# DDS_controller.net
KiCad netlist of a schematic drawn in Altium Designer
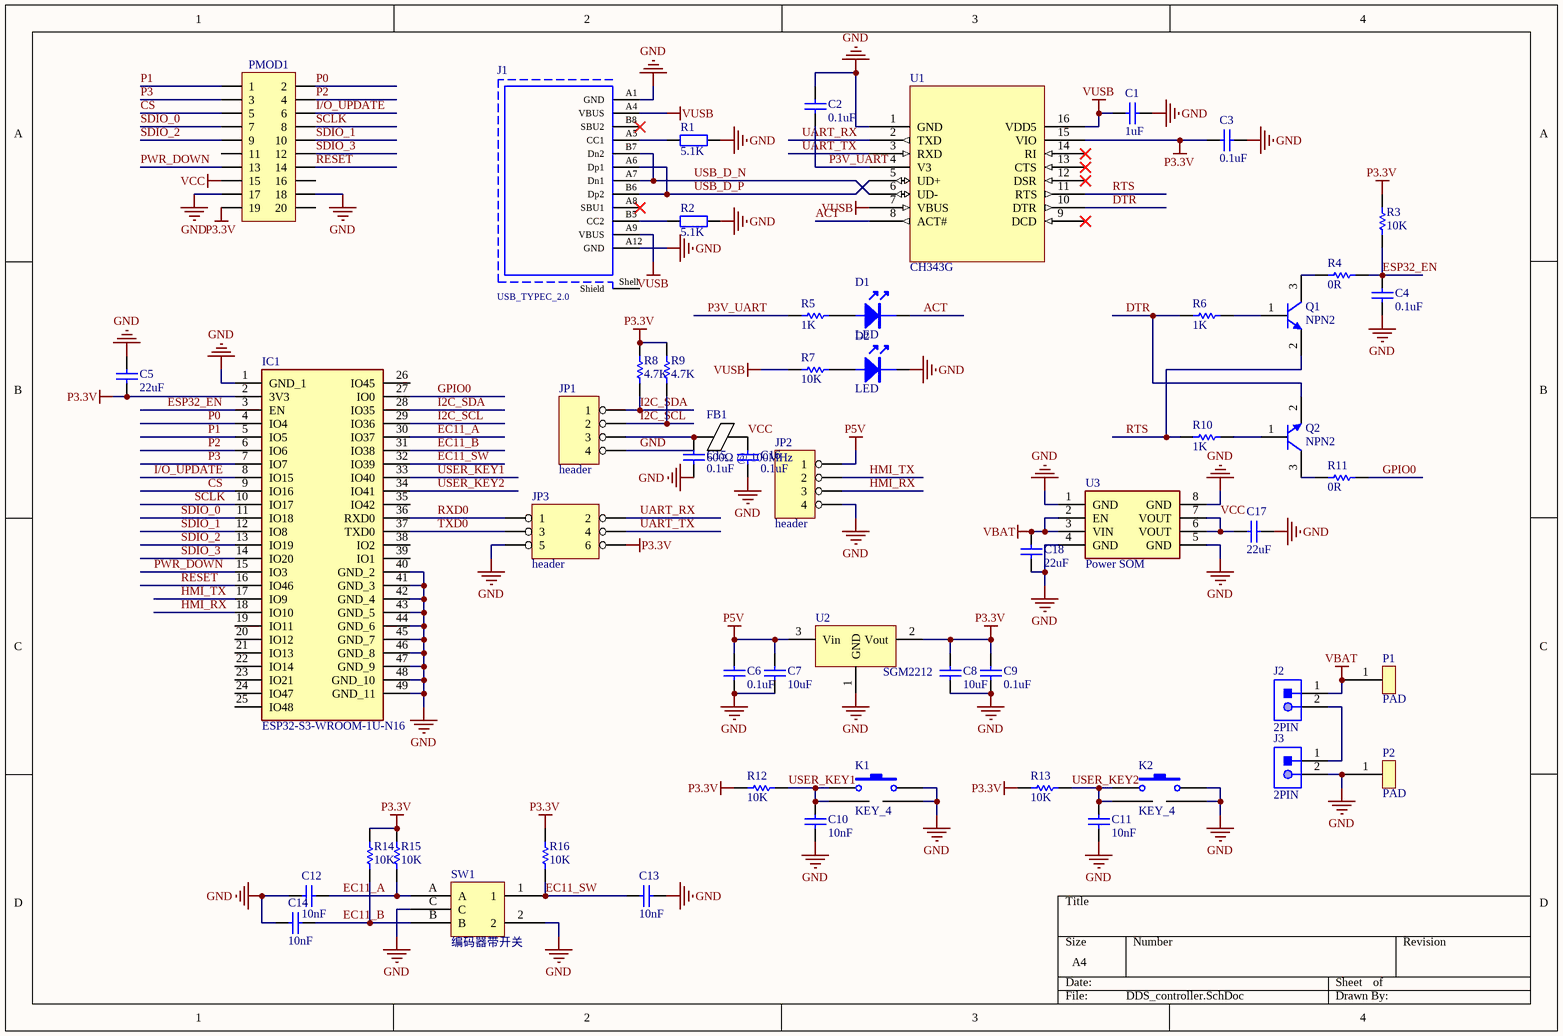
[diagram p0: DDS_controller.SchDoc]

(export (version "E")
  (design (tool "Eeschema 10.0.6"))
  (components
    (comp (ref "C1")
      (value "1uF")
      (footprint "0402L")
      (description "Capacitor")
      (fields (field (name "PUBLISHER") "Altium Limited"))
      (libsource (lib "My Footprint") (part "CAP"))
    )
    (comp (ref "C2")
      (value "0.1uF")
      (footprint "0402L")
      (description "Capacitor")
      (fields (field (name "PUBLISHER") "Altium Limited"))
      (libsource (lib "My Footprint") (part "CAP"))
    )
    (comp (ref "C3")
      (value "0.1uF")
      (footprint "0402L")
      (description "Capacitor")
      (fields (field (name "PUBLISHER") "Altium Limited"))
      (libsource (lib "My Footprint") (part "CAP"))
    )
    (comp (ref "C4")
      (value "0.1uF")
      (footprint "0402L")
      (description "Capacitor")
      (fields (field (name "PUBLISHER") "Altium Limited"))
      (libsource (lib "My Footprint") (part "CAP"))
    )
    (comp (ref "C5")
      (value "22uF")
      (footprint "0805")
      (description "Capacitor")
      (fields (field (name "PUBLISHER") "Altium Limited"))
      (libsource (lib "My Footprint") (part "CAP"))
    )
    (comp (ref "C6")
      (value "0.1uF")
      (footprint "0402L")
      (description "Capacitor")
      (fields (field (name "PUBLISHER") "Altium Limited"))
      (libsource (lib "My Footprint") (part "CAP"))
    )
    (comp (ref "C7")
      (value "10uF")
      (footprint "0805")
      (description "Capacitor")
      (fields (field (name "PUBLISHER") "Altium Limited"))
      (libsource (lib "My Footprint") (part "CAP"))
    )
    (comp (ref "C8")
      (value "10uF")
      (footprint "0805")
      (description "Capacitor")
      (fields (field (name "PUBLISHER") "Altium Limited"))
      (libsource (lib "My Footprint") (part "CAP"))
    )
    (comp (ref "C9")
      (value "0.1uF")
      (footprint "0402L")
      (description "Capacitor")
      (fields (field (name "PUBLISHER") "Altium Limited"))
      (libsource (lib "My Footprint") (part "CAP"))
    )
    (comp (ref "C10")
      (value "10nF")
      (footprint "0402L")
      (description "Capacitor")
      (fields (field (name "PUBLISHER") "Altium Limited"))
      (libsource (lib "My Footprint") (part "CAP"))
    )
    (comp (ref "C11")
      (value "10nF")
      (footprint "0402L")
      (description "Capacitor")
      (fields (field (name "PUBLISHER") "Altium Limited"))
      (libsource (lib "My Footprint") (part "CAP"))
    )
    (comp (ref "C12")
      (value "10nF")
      (footprint "0402L")
      (description "Capacitor")
      (fields (field (name "PUBLISHER") "Altium Limited"))
      (libsource (lib "My Footprint") (part "CAP"))
    )
    (comp (ref "C13")
      (value "10nF")
      (footprint "0402L")
      (description "Capacitor")
      (fields (field (name "PUBLISHER") "Altium Limited"))
      (libsource (lib "My Footprint") (part "CAP"))
    )
    (comp (ref "C14")
      (value "10nF")
      (footprint "0402L")
      (description "Capacitor")
      (fields (field (name "PUBLISHER") "Altium Limited"))
      (libsource (lib "My Footprint") (part "CAP"))
    )
    (comp (ref "C15")
      (value "0.1uF")
      (footprint "0603_C")
      (description "Capacitor")
      (fields (field (name "PUBLISHER") "Altium Limited"))
      (libsource (lib "My Footprint") (part "CAP"))
    )
    (comp (ref "C16")
      (value "0.1uF")
      (footprint "0603_C")
      (description "Capacitor")
      (fields (field (name "PUBLISHER") "Altium Limited"))
      (libsource (lib "My Footprint") (part "CAP"))
    )
    (comp (ref "C17")
      (value "22uF")
      (footprint "0805")
      (description "Capacitor")
      (fields (field (name "PUBLISHER") "Altium Limited"))
      (libsource (lib "My Footprint") (part "CAP"))
    )
    (comp (ref "C18")
      (value "22uF")
      (footprint "0805")
      (description "Capacitor")
      (fields (field (name "PUBLISHER") "Altium Limited"))
      (libsource (lib "My Footprint") (part "CAP"))
    )
    (comp (ref "D1")
      (value "LED")
      (footprint "0603_LED")
      (description "LED 发光二极管")
      (libsource (lib "My Footprint") (part "LED"))
    )
    (comp (ref "D2")
      (value "LED")
      (footprint "0603_LED")
      (description "LED 发光二极管")
      (libsource (lib "My Footprint") (part "LED"))
    )
    (comp (ref "FB1")
      (value "600Ω @ 100MHz")
      (footprint "0805")
      (description "磁珠 600Ω @ 100MHz")
      (libsource (lib "My Footprint") (part "FB"))
    )
    (comp (ref "IC1")
      (value "ESP32-S3-WROOM-1U-N16")
      (footprint "SamacSys:ESP32S3WROOM1UN16")
      (description "Integrated Circuit")
      (fields (field (name "MOUSER PART NUMBER") "356-ESP32S3WROM1UN16"))
      (libsource (lib "SamacSys") (part "ESP32-S3-WROOM-1U-N16"))
    )
    (comp (ref "J1")
      (value "USB_TYPEC_2.0")
      (footprint "USB_TYPEC_2.0_Horizontal_SMT")
      (description "USB 3.1 Type C Receptacle WR-COM, Horizontal, SMT / THT")
      (fields (field (name "PART NUMBER") "632723300011") (field (name "PUBLISHER") "Wurth Elektronik"))
      (libsource (lib "RegenovoPcbLib") (part "USB_TYPEC_2.0"))
    )
    (comp (ref "J2")
      (value "2PIN")
      (footprint "XH2.54-LI-2P")
      (libsource (lib "My Footprint") (part "HEADER 2PIN"))
    )
    (comp (ref "J3")
      (value "2PIN")
      (footprint "XH2.54-LI-2P")
      (libsource (lib "My Footprint") (part "HEADER 2PIN"))
    )
    (comp (ref "JP1")
      (value "header")
      (footprint "header4")
      (libsource (lib "My Footprint") (part "HEADER 4"))
    )
    (comp (ref "JP2")
      (value "header")
      (footprint "header4")
      (libsource (lib "My Footprint") (part "HEADER 4"))
    )
    (comp (ref "JP3")
      (value "header")
      (footprint "header2X3")
      (libsource (lib "My Footprint") (part "HEADER 3X2"))
    )
    (comp (ref "K1")
      (value "KEY_4")
      (footprint "KEY5*5")
      (description "Switch")
      (fields (field (name "PUBLISHER") "Altium Limited"))
      (libsource (lib "My Footprint") (part "KEY_4"))
    )
    (comp (ref "K2")
      (value "KEY_4")
      (footprint "KEY5*5")
      (description "Switch")
      (fields (field (name "PUBLISHER") "Altium Limited"))
      (libsource (lib "My Footprint") (part "KEY_4"))
    )
    (comp (ref "P1") (value "PAD") (footprint "PAD") (libsource (lib "My Footprint") (part "PAD")))
    (comp (ref "P2") (value "PAD") (footprint "PAD") (libsource (lib "My Footprint") (part "PAD")))
    (comp (ref "PMOD1")
      (value "Header 2X10")
      (footprint "header2X10")
      (description "10*2P接插件")
      (libsource (lib "2x10_PMOD") (part "Header 10X2"))
    )
    (comp (ref "Q1")
      (value "NPN2")
      (footprint "SOT-23-3")
      (description "贴片")
      (libsource (lib "My Footprint") (part "NPN2"))
    )
    (comp (ref "Q2")
      (value "NPN2")
      (footprint "SOT-23-3")
      (description "贴片")
      (libsource (lib "My Footprint") (part "NPN2"))
    )
    (comp (ref "R1")
      (value "5.1K")
      (footprint "R0402")
      (description "Resistor")
      (fields (field (name "Comment") "Res") (field (name "PUBLISHER") "Altium Limited"))
      (libsource (lib "RegenovoPcbLib") (part "Res"))
    )
    (comp (ref "R2")
      (value "5.1K")
      (footprint "R0402")
      (description "Resistor")
      (fields (field (name "Comment") "Res") (field (name "PUBLISHER") "Altium Limited"))
      (libsource (lib "RegenovoPcbLib") (part "Res"))
    )
    (comp (ref "R3")
      (value "10K")
      (footprint "0402L")
      (description "Resistor")
      (fields (field (name "PUBLISHER") "Altium Limited"))
      (libsource (lib "My Footprint") (part "RES"))
    )
    (comp (ref "R4")
      (value "0R")
      (footprint "0402L")
      (description "Resistor")
      (fields (field (name "PUBLISHER") "Altium Limited"))
      (libsource (lib "My Footprint") (part "RES"))
    )
    (comp (ref "R5")
      (value "1K")
      (footprint "0402L")
      (description "Resistor")
      (fields (field (name "PUBLISHER") "Altium Limited"))
      (libsource (lib "My Footprint") (part "RES"))
    )
    (comp (ref "R6")
      (value "1K")
      (footprint "0402L")
      (description "Resistor")
      (fields (field (name "PUBLISHER") "Altium Limited"))
      (libsource (lib "My Footprint") (part "RES"))
    )
    (comp (ref "R7")
      (value "10K")
      (footprint "0402L")
      (description "Resistor")
      (fields (field (name "PUBLISHER") "Altium Limited"))
      (libsource (lib "My Footprint") (part "RES"))
    )
    (comp (ref "R8")
      (value "4.7K")
      (footprint "0402L")
      (description "Resistor")
      (fields (field (name "PUBLISHER") "Altium Limited"))
      (libsource (lib "My Footprint") (part "RES"))
    )
    (comp (ref "R9")
      (value "4.7K")
      (footprint "0402L")
      (description "Resistor")
      (fields (field (name "PUBLISHER") "Altium Limited"))
      (libsource (lib "My Footprint") (part "RES"))
    )
    (comp (ref "R10")
      (value "1K")
      (footprint "0402L")
      (description "Resistor")
      (fields (field (name "PUBLISHER") "Altium Limited"))
      (libsource (lib "My Footprint") (part "RES"))
    )
    (comp (ref "R11")
      (value "0R")
      (footprint "0402L")
      (description "Resistor")
      (fields (field (name "PUBLISHER") "Altium Limited"))
      (libsource (lib "My Footprint") (part "RES"))
    )
    (comp (ref "R12")
      (value "10K")
      (footprint "0402L")
      (description "Resistor")
      (fields (field (name "PUBLISHER") "Altium Limited"))
      (libsource (lib "My Footprint") (part "RES"))
    )
    (comp (ref "R13")
      (value "10K")
      (footprint "0402L")
      (description "Resistor")
      (fields (field (name "PUBLISHER") "Altium Limited"))
      (libsource (lib "My Footprint") (part "RES"))
    )
    (comp (ref "R14")
      (value "10K")
      (footprint "0402L")
      (description "Resistor")
      (fields (field (name "PUBLISHER") "Altium Limited"))
      (libsource (lib "My Footprint") (part "RES"))
    )
    (comp (ref "R15")
      (value "10K")
      (footprint "0402L")
      (description "Resistor")
      (fields (field (name "PUBLISHER") "Altium Limited"))
      (libsource (lib "My Footprint") (part "RES"))
    )
    (comp (ref "R16")
      (value "10K")
      (footprint "0402L")
      (description "Resistor")
      (fields (field (name "PUBLISHER") "Altium Limited"))
      (libsource (lib "My Footprint") (part "RES"))
    )
    (comp (ref "SW1") (value "编码器带开关") (footprint "EC11") (libsource (lib "My Footprint") (part "EC11")))
    (comp (ref "U1")
      (value "CH343G")
      (footprint "SOP16")
      (description "USB to high speed enhanced TTL Serial / UART")
      (libsource (lib "SamacSys") (part "CH343G"))
    )
    (comp (ref "U2")
      (value "SGM2212")
      (footprint "SOT-223")
      (description "3.3V电压转换器AMS1117")
      (libsource (lib "My Footprint") (part "AMS1117"))
    )
    (comp (ref "U3")
      (value "Power SOM")
      (footprint "7A8300")
      (libsource (lib "power_module") (part "TPS7A8300"))
    )
  )
  (nets
    (net (code "1") (name "/ACT") (class "Default")
      (node (ref "D1") (pin "1") (pinfunction "K_1") (pintype "passive"))
      (node (ref "U1") (pin "8") (pinfunction "ACT#_8") (pintype "output"))
    )
    (net (code "2") (name "/CS") (class "Default")
      (node (ref "IC1") (pin "9") (pinfunction "IO16_9") (pintype "passive"))
      (node (ref "PMOD1") (pin "5") (pinfunction "5_5") (pintype "passive"))
    )
    (net (code "3") (name "/DTR") (class "Default")
      (node (ref "Q2") (pin "2") (pinfunction "E_2") (pintype "passive"))
      (node (ref "R6") (pin "1") (pinfunction "1_1") (pintype "passive"))
      (node (ref "U1") (pin "10") (pinfunction "DTR_10") (pintype "output"))
    )
    (net (code "4") (name "/EC11_A") (class "Default")
      (node (ref "C12") (pin "2") (pinfunction "2_2") (pintype "passive"))
      (node (ref "IC1") (pin "30") (pinfunction "IO37_30") (pintype "passive"))
      (node (ref "R15") (pin "1") (pinfunction "1_1") (pintype "passive"))
      (node (ref "SW1") (pin "A") (pinfunction "A_A") (pintype "passive"))
    )
    (net (code "5") (name "/EC11_B") (class "Default")
      (node (ref "C14") (pin "2") (pinfunction "2_2") (pintype "passive"))
      (node (ref "IC1") (pin "31") (pinfunction "IO38_31") (pintype "passive"))
      (node (ref "R14") (pin "1") (pinfunction "1_1") (pintype "passive"))
      (node (ref "SW1") (pin "B") (pinfunction "B_B") (pintype "passive"))
    )
    (net (code "6") (name "/EC11_SW") (class "Default")
      (node (ref "C13") (pin "2") (pinfunction "2_2") (pintype "passive"))
      (node (ref "IC1") (pin "32") (pinfunction "IO39_32") (pintype "passive"))
      (node (ref "R16") (pin "1") (pinfunction "1_1") (pintype "passive"))
      (node (ref "SW1") (pin "1") (pinfunction "1_1") (pintype "passive"))
    )
    (net (code "7") (name "/ESP32_EN") (class "Default")
      (node (ref "C4") (pin "2") (pinfunction "2_2") (pintype "passive"))
      (node (ref "IC1") (pin "3") (pinfunction "EN_3") (pintype "passive"))
      (node (ref "R3") (pin "1") (pinfunction "1_1") (pintype "passive"))
      (node (ref "R4") (pin "2") (pinfunction "2_2") (pintype "passive"))
    )
    (net (code "8") (name "/GPIO0") (class "Default")
      (node (ref "IC1") (pin "27") (pinfunction "IO0_27") (pintype "passive"))
      (node (ref "R11") (pin "2") (pinfunction "2_2") (pintype "passive"))
    )
    (net (code "9") (name "/HMI_RX") (class "Default")
      (node (ref "IC1") (pin "18") (pinfunction "IO10_18") (pintype "passive"))
      (node (ref "JP2") (pin "3") (pinfunction "3_3") (pintype "passive"))
    )
    (net (code "10") (name "/HMI_TX") (class "Default")
      (node (ref "IC1") (pin "17") (pinfunction "IO9_17") (pintype "passive"))
      (node (ref "JP2") (pin "2") (pinfunction "2_2") (pintype "passive"))
    )
    (net (code "11") (name "/I2C_SCL") (class "Default")
      (node (ref "IC1") (pin "29") (pinfunction "IO36_29") (pintype "passive"))
      (node (ref "JP1") (pin "2") (pinfunction "2_2") (pintype "passive"))
      (node (ref "R9") (pin "1") (pinfunction "1_1") (pintype "passive"))
    )
    (net (code "12") (name "/I2C_SDA") (class "Default")
      (node (ref "IC1") (pin "28") (pinfunction "IO35_28") (pintype "passive"))
      (node (ref "JP1") (pin "1") (pinfunction "1_1") (pintype "passive"))
      (node (ref "R8") (pin "1") (pinfunction "1_1") (pintype "passive"))
    )
    (net (code "13") (name "/I{slash}O_UPDATE") (class "Default")
      (node (ref "IC1") (pin "8") (pinfunction "IO15_8") (pintype "passive"))
      (node (ref "PMOD1") (pin "6") (pinfunction "6_6") (pintype "passive"))
    )
    (net (code "14") (name "/P0") (class "Default")
      (node (ref "IC1") (pin "4") (pinfunction "IO4_4") (pintype "passive"))
      (node (ref "PMOD1") (pin "2") (pinfunction "2_2") (pintype "passive"))
    )
    (net (code "15") (name "/P1") (class "Default")
      (node (ref "IC1") (pin "5") (pinfunction "IO5_5") (pintype "passive"))
      (node (ref "PMOD1") (pin "1") (pinfunction "1_1") (pintype "passive"))
    )
    (net (code "16") (name "/P2") (class "Default")
      (node (ref "IC1") (pin "6") (pinfunction "IO6_6") (pintype "passive"))
      (node (ref "PMOD1") (pin "4") (pinfunction "4_4") (pintype "passive"))
    )
    (net (code "17") (name "/P3") (class "Default")
      (node (ref "IC1") (pin "7") (pinfunction "IO7_7") (pintype "passive"))
      (node (ref "PMOD1") (pin "3") (pinfunction "3_3") (pintype "passive"))
    )
    (net (code "18") (name "/P3V_UART") (class "Default")
      (node (ref "C2") (pin "1") (pinfunction "1_1") (pintype "passive"))
      (node (ref "R5") (pin "1") (pinfunction "1_1") (pintype "passive"))
      (node (ref "U1") (pin "4") (pinfunction "V3_4") (pintype "power_in"))
    )
    (net (code "19") (name "/PWR_DOWN") (class "Default")
      (node (ref "IC1") (pin "15") (pinfunction "IO3_15") (pintype "passive"))
      (node (ref "PMOD1") (pin "13") (pinfunction "13_13") (pintype "passive"))
    )
    (net (code "20") (name "/RESET") (class "Default")
      (node (ref "IC1") (pin "16") (pinfunction "IO46_16") (pintype "passive"))
      (node (ref "PMOD1") (pin "14") (pinfunction "14_14") (pintype "passive"))
    )
    (net (code "21") (name "/RTS") (class "Default")
      (node (ref "Q1") (pin "2") (pinfunction "E_2") (pintype "passive"))
      (node (ref "R10") (pin "1") (pinfunction "1_1") (pintype "passive"))
      (node (ref "U1") (pin "11") (pinfunction "RTS_11") (pintype "output"))
    )
    (net (code "22") (name "/RXD0") (class "Default")
      (node (ref "IC1") (pin "36") (pinfunction "RXD0_36") (pintype "passive"))
      (node (ref "JP3") (pin "1") (pinfunction "1_1") (pintype "passive"))
    )
    (net (code "23") (name "/SCLK") (class "Default")
      (node (ref "IC1") (pin "10") (pinfunction "IO17_10") (pintype "passive"))
      (node (ref "PMOD1") (pin "8") (pinfunction "8_8") (pintype "passive"))
    )
    (net (code "24") (name "/SDIO_0") (class "Default")
      (node (ref "IC1") (pin "11") (pinfunction "IO18_11") (pintype "passive"))
      (node (ref "PMOD1") (pin "7") (pinfunction "7_7") (pintype "passive"))
    )
    (net (code "25") (name "/SDIO_1") (class "Default")
      (node (ref "IC1") (pin "12") (pinfunction "IO8_12") (pintype "passive"))
      (node (ref "PMOD1") (pin "10") (pinfunction "10_10") (pintype "passive"))
    )
    (net (code "26") (name "/SDIO_2") (class "Default")
      (node (ref "IC1") (pin "13") (pinfunction "IO19_13") (pintype "passive"))
      (node (ref "PMOD1") (pin "9") (pinfunction "9_9") (pintype "passive"))
    )
    (net (code "27") (name "/SDIO_3") (class "Default")
      (node (ref "IC1") (pin "14") (pinfunction "IO20_14") (pintype "passive"))
      (node (ref "PMOD1") (pin "12") (pinfunction "12_12") (pintype "passive"))
    )
    (net (code "28") (name "/TXD0") (class "Default")
      (node (ref "IC1") (pin "37") (pinfunction "TXD0_37") (pintype "passive"))
      (node (ref "JP3") (pin "3") (pinfunction "3_3") (pintype "passive"))
    )
    (net (code "29") (name "/UART_RX") (class "Default")
      (node (ref "JP3") (pin "2") (pinfunction "2_2") (pintype "passive"))
      (node (ref "U1") (pin "2") (pinfunction "TXD_2") (pintype "output"))
    )
    (net (code "30") (name "/UART_TX") (class "Default")
      (node (ref "JP3") (pin "4") (pinfunction "4_4") (pintype "passive"))
      (node (ref "U1") (pin "3") (pinfunction "RXD_3") (pintype "input"))
    )
    (net (code "31") (name "/USB_D_N") (class "Default")
      (node (ref "J1") (pin "A7") (pinfunction "Dn1_A7") (pintype "passive"))
      (node (ref "J1") (pin "B7") (pinfunction "Dn2_B7") (pintype "passive"))
      (node (ref "U1") (pin "6") (pinfunction "UD-_6") (pintype "bidirectional"))
    )
    (net (code "32") (name "/USB_D_P") (class "Default")
      (node (ref "J1") (pin "A6") (pinfunction "Dp1_A6") (pintype "passive"))
      (node (ref "J1") (pin "B6") (pinfunction "Dp2_B6") (pintype "passive"))
      (node (ref "U1") (pin "5") (pinfunction "UD+_5") (pintype "bidirectional"))
    )
    (net (code "33") (name "/USER_KEY1") (class "Default")
      (node (ref "C10") (pin "2") (pinfunction "2_2") (pintype "passive"))
      (node (ref "IC1") (pin "33") (pinfunction "IO40_33") (pintype "passive"))
      (node (ref "K1") (pin "1") (pinfunction "1_1") (pintype "passive"))
      (node (ref "K1") (pin "4") (pinfunction "4_4") (pintype "passive"))
      (node (ref "R12") (pin "1") (pinfunction "1_1") (pintype "passive"))
    )
    (net (code "34") (name "/USER_KEY2") (class "Default")
      (node (ref "C11") (pin "2") (pinfunction "2_2") (pintype "passive"))
      (node (ref "IC1") (pin "34") (pinfunction "IO41_34") (pintype "passive"))
      (node (ref "K2") (pin "1") (pinfunction "1_1") (pintype "passive"))
      (node (ref "K2") (pin "4") (pinfunction "4_4") (pintype "passive"))
      (node (ref "R13") (pin "1") (pinfunction "1_1") (pintype "passive"))
    )
    (net (code "35") (name "GND") (class "Default")
      (node (ref "C1") (pin "1") (pinfunction "1_1") (pintype "passive"))
      (node (ref "C10") (pin "1") (pinfunction "1_1") (pintype "passive"))
      (node (ref "C11") (pin "1") (pinfunction "1_1") (pintype "passive"))
      (node (ref "C12") (pin "1") (pinfunction "1_1") (pintype "passive"))
      (node (ref "C13") (pin "1") (pinfunction "1_1") (pintype "passive"))
      (node (ref "C14") (pin "1") (pinfunction "1_1") (pintype "passive"))
      (node (ref "C15") (pin "1") (pinfunction "1_1") (pintype "passive"))
      (node (ref "C16") (pin "1") (pinfunction "1_1") (pintype "passive"))
      (node (ref "C17") (pin "1") (pinfunction "1_1") (pintype "passive"))
      (node (ref "C18") (pin "2") (pinfunction "2_2") (pintype "passive"))
      (node (ref "C2") (pin "2") (pinfunction "2_2") (pintype "passive"))
      (node (ref "C3") (pin "2") (pinfunction "2_2") (pintype "passive"))
      (node (ref "C4") (pin "1") (pinfunction "1_1") (pintype "passive"))
      (node (ref "C5") (pin "2") (pinfunction "2_2") (pintype "passive"))
      (node (ref "C6") (pin "1") (pinfunction "1_1") (pintype "passive"))
      (node (ref "C7") (pin "1") (pinfunction "1_1") (pintype "passive"))
      (node (ref "C8") (pin "1") (pinfunction "1_1") (pintype "passive"))
      (node (ref "C9") (pin "1") (pinfunction "1_1") (pintype "passive"))
      (node (ref "D2") (pin "1") (pinfunction "K_1") (pintype "passive"))
      (node (ref "IC1") (pin "1") (pinfunction "GND_1_1") (pintype "passive"))
      (node (ref "IC1") (pin "40") (pinfunction "GND_2_40") (pintype "passive"))
      (node (ref "IC1") (pin "41") (pinfunction "GND_3_41") (pintype "passive"))
      (node (ref "IC1") (pin "42") (pinfunction "GND_4_42") (pintype "passive"))
      (node (ref "IC1") (pin "43") (pinfunction "GND_5_43") (pintype "passive"))
      (node (ref "IC1") (pin "44") (pinfunction "GND_6_44") (pintype "passive"))
      (node (ref "IC1") (pin "45") (pinfunction "GND_7_45") (pintype "passive"))
      (node (ref "IC1") (pin "46") (pinfunction "GND_8_46") (pintype "passive"))
      (node (ref "IC1") (pin "47") (pinfunction "GND_9_47") (pintype "passive"))
      (node (ref "IC1") (pin "48") (pinfunction "GND_10_48") (pintype "passive"))
      (node (ref "IC1") (pin "49") (pinfunction "GND_11_49") (pintype "passive"))
      (node (ref "J1") (pin "A1") (pinfunction "GND_A1") (pintype "passive"))
      (node (ref "J1") (pin "A12") (pinfunction "GND_A12") (pintype "passive"))
      (node (ref "J3") (pin "2") (pinfunction "2_2") (pintype "passive"))
      (node (ref "JP1") (pin "4") (pinfunction "4_4") (pintype "passive"))
      (node (ref "JP2") (pin "4") (pinfunction "4_4") (pintype "passive"))
      (node (ref "JP3") (pin "5") (pinfunction "5_5") (pintype "passive"))
      (node (ref "K1") (pin "2") (pinfunction "2_2") (pintype "passive"))
      (node (ref "K1") (pin "3") (pinfunction "3_3") (pintype "passive"))
      (node (ref "K2") (pin "2") (pinfunction "2_2") (pintype "passive"))
      (node (ref "K2") (pin "3") (pinfunction "3_3") (pintype "passive"))
      (node (ref "P2") (pin "1") (pintype "passive"))
      (node (ref "PMOD1") (pin "17") (pinfunction "17_17") (pintype "passive"))
      (node (ref "PMOD1") (pin "18") (pinfunction "18_18") (pintype "passive"))
      (node (ref "R1") (pin "2") (pinfunction "2_2") (pintype "passive"))
      (node (ref "R2") (pin "2") (pinfunction "2_2") (pintype "passive"))
      (node (ref "SW1") (pin "2") (pinfunction "2_2") (pintype "passive"))
      (node (ref "SW1") (pin "C") (pinfunction "C_C") (pintype "passive"))
      (node (ref "U1") (pin "1") (pinfunction "GND_1") (pintype "power_in"))
      (node (ref "U2") (pin "1") (pinfunction "GND_1") (pintype "passive"))
      (node (ref "U3") (pin "1") (pinfunction "GND_1") (pintype "passive"))
      (node (ref "U3") (pin "4") (pinfunction "GND_4") (pintype "passive"))
      (node (ref "U3") (pin "5") (pinfunction "GND_5") (pintype "passive"))
      (node (ref "U3") (pin "8") (pinfunction "GND_8") (pintype "passive"))
    )
    (net (code "36") (name "Net-(C15-Pad2)") (class "Default")
      (node (ref "C15") (pin "2") (pinfunction "2_2") (pintype "passive"))
      (node (ref "FB1") (pin "1") (pinfunction "1_1") (pintype "passive"))
      (node (ref "JP1") (pin "3") (pinfunction "3_3") (pintype "passive"))
    )
    (net (code "37") (name "Net-(D1-A)") (class "Default")
      (node (ref "D1") (pin "2") (pinfunction "A_2") (pintype "passive"))
      (node (ref "R5") (pin "2") (pinfunction "2_2") (pintype "passive"))
    )
    (net (code "38") (name "Net-(D2-A)") (class "Default")
      (node (ref "D2") (pin "2") (pinfunction "A_2") (pintype "passive"))
      (node (ref "R7") (pin "2") (pinfunction "2_2") (pintype "passive"))
    )
    (net (code "39") (name "Net-(J1-CC1)") (class "Default")
      (node (ref "J1") (pin "A5") (pinfunction "CC1_A5") (pintype "passive"))
      (node (ref "R1") (pin "1") (pinfunction "1_1") (pintype "passive"))
    )
    (net (code "40") (name "Net-(J1-CC2)") (class "Default")
      (node (ref "J1") (pin "B5") (pinfunction "CC2_B5") (pintype "passive"))
      (node (ref "R2") (pin "1") (pinfunction "1_1") (pintype "passive"))
    )
    (net (code "41") (name "Net-(J2-Pad2)") (class "Default")
      (node (ref "J2") (pin "2") (pinfunction "2_2") (pintype "passive"))
      (node (ref "J3") (pin "1") (pinfunction "1_1") (pintype "passive"))
    )
    (net (code "42") (name "Net-(Q1-B)") (class "Default")
      (node (ref "Q1") (pin "1") (pinfunction "B_1") (pintype "passive"))
      (node (ref "R6") (pin "2") (pinfunction "2_2") (pintype "passive"))
    )
    (net (code "43") (name "Net-(Q1-C)") (class "Default")
      (node (ref "Q1") (pin "3") (pinfunction "C_3") (pintype "passive"))
      (node (ref "R4") (pin "1") (pinfunction "1_1") (pintype "passive"))
    )
    (net (code "44") (name "Net-(Q2-B)") (class "Default")
      (node (ref "Q2") (pin "1") (pinfunction "B_1") (pintype "passive"))
      (node (ref "R10") (pin "2") (pinfunction "2_2") (pintype "passive"))
    )
    (net (code "45") (name "Net-(Q2-C)") (class "Default")
      (node (ref "Q2") (pin "3") (pinfunction "C_3") (pintype "passive"))
      (node (ref "R11") (pin "1") (pinfunction "1_1") (pintype "passive"))
    )
    (net (code "46") (name "P3.3V") (class "Default")
      (node (ref "C3") (pin "1") (pinfunction "1_1") (pintype "passive"))
      (node (ref "C5") (pin "1") (pinfunction "1_1") (pintype "passive"))
      (node (ref "C8") (pin "2") (pinfunction "2_2") (pintype "passive"))
      (node (ref "C9") (pin "2") (pinfunction "2_2") (pintype "passive"))
      (node (ref "IC1") (pin "2") (pinfunction "3V3_2") (pintype "passive"))
      (node (ref "JP3") (pin "6") (pinfunction "6_6") (pintype "passive"))
      (node (ref "PMOD1") (pin "19") (pinfunction "19_19") (pintype "passive"))
      (node (ref "R12") (pin "2") (pinfunction "2_2") (pintype "passive"))
      (node (ref "R13") (pin "2") (pinfunction "2_2") (pintype "passive"))
      (node (ref "R14") (pin "2") (pinfunction "2_2") (pintype "passive"))
      (node (ref "R15") (pin "2") (pinfunction "2_2") (pintype "passive"))
      (node (ref "R16") (pin "2") (pinfunction "2_2") (pintype "passive"))
      (node (ref "R3") (pin "2") (pinfunction "2_2") (pintype "passive"))
      (node (ref "R8") (pin "2") (pinfunction "2_2") (pintype "passive"))
      (node (ref "R9") (pin "2") (pinfunction "2_2") (pintype "passive"))
      (node (ref "U1") (pin "15") (pinfunction "VIO_15") (pintype "power_in"))
      (node (ref "U2") (pin "2") (pinfunction "Vout_2") (pintype "passive"))
    )
    (net (code "47") (name "P5V") (class "Default")
      (node (ref "C6") (pin "2") (pinfunction "2_2") (pintype "passive"))
      (node (ref "C7") (pin "2") (pinfunction "2_2") (pintype "passive"))
      (node (ref "JP2") (pin "1") (pinfunction "1_1") (pintype "passive"))
      (node (ref "U2") (pin "3") (pinfunction "Vin_3") (pintype "passive"))
    )
    (net (code "48") (name "VBAT") (class "Default")
      (node (ref "C18") (pin "1") (pinfunction "1_1") (pintype "passive"))
      (node (ref "J2") (pin "1") (pinfunction "1_1") (pintype "passive"))
      (node (ref "P1") (pin "1") (pintype "passive"))
      (node (ref "U3") (pin "2") (pinfunction "EN_2") (pintype "passive"))
      (node (ref "U3") (pin "3") (pinfunction "VIN_3") (pintype "passive"))
    )
    (net (code "49") (name "VCC") (class "Default")
      (node (ref "C16") (pin "2") (pinfunction "2_2") (pintype "passive"))
      (node (ref "C17") (pin "2") (pinfunction "2_2") (pintype "passive"))
      (node (ref "FB1") (pin "2") (pinfunction "2_2") (pintype "passive"))
      (node (ref "PMOD1") (pin "15") (pinfunction "15_15") (pintype "passive"))
      (node (ref "U3") (pin "6") (pinfunction "VOUT_6") (pintype "passive"))
      (node (ref "U3") (pin "7") (pinfunction "VOUT_7") (pintype "passive"))
    )
    (net (code "50") (name "VUSB") (class "Default")
      (node (ref "C1") (pin "2") (pinfunction "2_2") (pintype "passive"))
      (node (ref "J1") (pin "A4") (pinfunction "VBUS_A4") (pintype "passive"))
      (node (ref "J1") (pin "A9") (pinfunction "VBUS_A9") (pintype "passive"))
      (node (ref "R7") (pin "1") (pinfunction "1_1") (pintype "passive"))
      (node (ref "U1") (pin "16") (pinfunction "VDD5_16") (pintype "power_in"))
      (node (ref "U1") (pin "7") (pinfunction "VBUS_7") (pintype "input"))
    )
    (net (code "51") (name "unconnected-(IC1-IO1-Pad39)") (class "Default")
      (node (ref "IC1") (pin "39") (pinfunction "IO1_39") (pintype "passive"))
    )
    (net (code "52") (name "unconnected-(IC1-IO2-Pad38)") (class "Default")
      (node (ref "IC1") (pin "38") (pinfunction "IO2_38") (pintype "passive"))
    )
    (net (code "53") (name "unconnected-(IC1-IO11-Pad19)") (class "Default")
      (node (ref "IC1") (pin "19") (pinfunction "IO11_19") (pintype "passive"))
    )
    (net (code "54") (name "unconnected-(IC1-IO12-Pad20)") (class "Default")
      (node (ref "IC1") (pin "20") (pinfunction "IO12_20") (pintype "passive"))
    )
    (net (code "55") (name "unconnected-(IC1-IO13-Pad21)") (class "Default")
      (node (ref "IC1") (pin "21") (pinfunction "IO13_21") (pintype "passive"))
    )
    (net (code "56") (name "unconnected-(IC1-IO14-Pad22)") (class "Default")
      (node (ref "IC1") (pin "22") (pinfunction "IO14_22") (pintype "passive"))
    )
    (net (code "57") (name "unconnected-(IC1-IO21-Pad23)") (class "Default")
      (node (ref "IC1") (pin "23") (pinfunction "IO21_23") (pintype "passive"))
    )
    (net (code "58") (name "unconnected-(IC1-IO42-Pad35)") (class "Default")
      (node (ref "IC1") (pin "35") (pinfunction "IO42_35") (pintype "passive"))
    )
    (net (code "59") (name "unconnected-(IC1-IO45-Pad26)") (class "Default")
      (node (ref "IC1") (pin "26") (pinfunction "IO45_26") (pintype "passive"))
    )
    (net (code "60") (name "unconnected-(IC1-IO47-Pad24)") (class "Default")
      (node (ref "IC1") (pin "24") (pinfunction "IO47_24") (pintype "passive"))
    )
    (net (code "61") (name "unconnected-(IC1-IO48-Pad25)") (class "Default")
      (node (ref "IC1") (pin "25") (pinfunction "IO48_25") (pintype "passive"))
    )
    (net (code "62") (name "unconnected-(J1-SBU1-PadA8)") (class "Default")
      (node (ref "J1") (pin "A8") (pinfunction "SBU1_A8") (pintype "passive+no_connect"))
    )
    (net (code "63") (name "unconnected-(J1-SBU2-PadB8)") (class "Default")
      (node (ref "J1") (pin "B8") (pinfunction "SBU2_B8") (pintype "passive+no_connect"))
    )
    (net (code "64") (name "unconnected-(J1-Shield-PadShell)") (class "Default")
      (node (ref "J1") (pin "Shell") (pinfunction "Shield_Shell") (pintype "passive"))
    )
    (net (code "65") (name "unconnected-(PMOD1-Pad11)") (class "Default")
      (node (ref "PMOD1") (pin "11") (pinfunction "11_11") (pintype "passive"))
    )
    (net (code "66") (name "unconnected-(PMOD1-Pad16)") (class "Default")
      (node (ref "PMOD1") (pin "16") (pinfunction "16_16") (pintype "passive"))
    )
    (net (code "67") (name "unconnected-(PMOD1-Pad20)") (class "Default")
      (node (ref "PMOD1") (pin "20") (pinfunction "20_20") (pintype "passive"))
    )
    (net (code "68") (name "unconnected-(U1-CTS-Pad13)") (class "Default")
      (node (ref "U1") (pin "13") (pinfunction "CTS_13") (pintype "input+no_connect"))
    )
    (net (code "69") (name "unconnected-(U1-DCD-Pad9)") (class "Default")
      (node (ref "U1") (pin "9") (pinfunction "DCD_9") (pintype "input+no_connect"))
    )
    (net (code "70") (name "unconnected-(U1-DSR-Pad12)") (class "Default")
      (node (ref "U1") (pin "12") (pinfunction "DSR_12") (pintype "input+no_connect"))
    )
    (net (code "71") (name "unconnected-(U1-RI-Pad14)") (class "Default")
      (node (ref "U1") (pin "14") (pinfunction "RI_14") (pintype "input+no_connect"))
    )
  )
)
